# BoardB-Python.net
KiCad netlist of a schematic drawn in Altium Designer
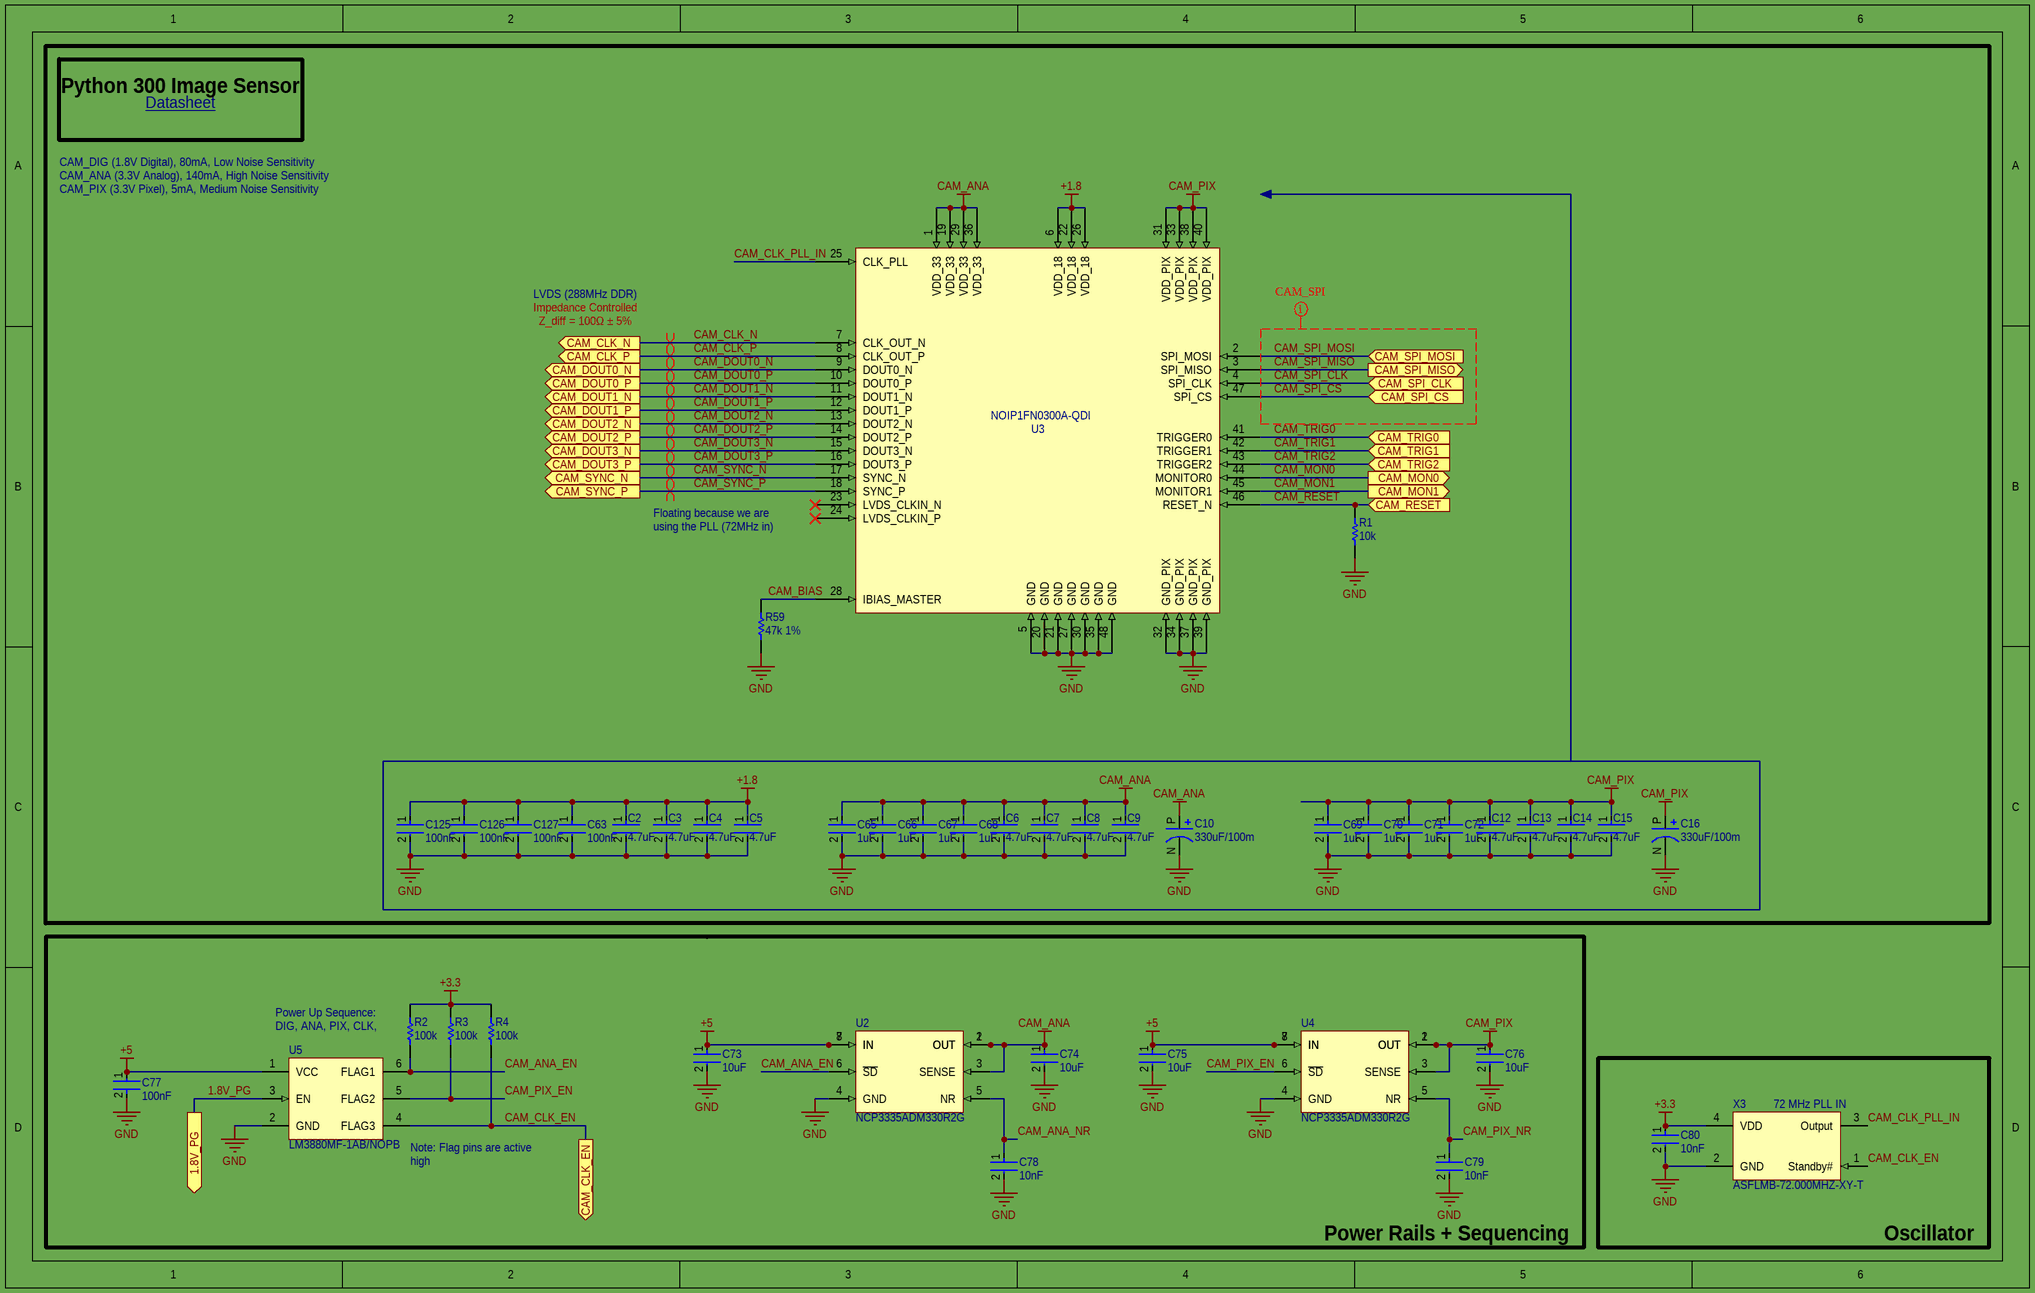
[diagram p0: BoardB-Python.SchDoc]

(export (version "E")
  (design (tool "Eeschema 10.0.6"))
  (components
    (comp (ref "C2")
      (value "4.7uF")
      (footprint "FP-GRM155-0_1-IPC_B")
      (description "Chip Multilayer Ceramic Capacitors for General Purpose, 0402, 4.7uF, X5R, 15%, 20%, 6.3V")
      (fields (field (name "VOLTAGE") "6.3V") (field (name "TOLERANCE") "20%"))
      (libsource (lib "Altium Content Vault") (part "11868f565c42a9108669ba33697ecf6"))
    )
    (comp (ref "C3")
      (value "4.7uF")
      (footprint "FP-GRM155-0_1-IPC_B")
      (description "Chip Multilayer Ceramic Capacitors for General Purpose, 0402, 4.7uF, X5R, 15%, 20%, 6.3V")
      (fields (field (name "VOLTAGE") "6.3V") (field (name "TOLERANCE") "20%"))
      (libsource (lib "Altium Content Vault") (part "11868f565c42a9108669ba33697ecf6"))
    )
    (comp (ref "C4")
      (value "4.7uF")
      (footprint "FP-GRM155-0_1-IPC_B")
      (description "Chip Multilayer Ceramic Capacitors for General Purpose, 0402, 4.7uF, X5R, 15%, 20%, 6.3V")
      (fields (field (name "VOLTAGE") "6.3V") (field (name "TOLERANCE") "20%"))
      (libsource (lib "Altium Content Vault") (part "11868f565c42a9108669ba33697ecf6"))
    )
    (comp (ref "C5")
      (value "4.7uF")
      (footprint "FP-GRM155-0_1-IPC_B")
      (description "Chip Multilayer Ceramic Capacitors for General Purpose, 0402, 4.7uF, X5R, 15%, 20%, 6.3V")
      (fields (field (name "VOLTAGE") "6.3V") (field (name "TOLERANCE") "20%"))
      (libsource (lib "Altium Content Vault") (part "11868f565c42a9108669ba33697ecf6"))
    )
    (comp (ref "C6")
      (value "4.7uF")
      (footprint "FP-GRM155-0_1-IPC_B")
      (description "Chip Multilayer Ceramic Capacitors for General Purpose, 0402, 4.7uF, X5R, 15%, 20%, 6.3V")
      (fields (field (name "VOLTAGE") "6.3V") (field (name "TOLERANCE") "20%"))
      (libsource (lib "Altium Content Vault") (part "11868f565c42a9108669ba33697ecf6"))
    )
    (comp (ref "C7")
      (value "4.7uF")
      (footprint "FP-GRM155-0_1-IPC_B")
      (description "Chip Multilayer Ceramic Capacitors for General Purpose, 0402, 4.7uF, X5R, 15%, 20%, 6.3V")
      (fields (field (name "VOLTAGE") "6.3V") (field (name "TOLERANCE") "20%"))
      (libsource (lib "Altium Content Vault") (part "11868f565c42a9108669ba33697ecf6"))
    )
    (comp (ref "C8")
      (value "4.7uF")
      (footprint "FP-GRM155-0_1-IPC_B")
      (description "Chip Multilayer Ceramic Capacitors for General Purpose, 0402, 4.7uF, X5R, 15%, 20%, 6.3V")
      (fields (field (name "VOLTAGE") "6.3V") (field (name "TOLERANCE") "20%"))
      (libsource (lib "Altium Content Vault") (part "11868f565c42a9108669ba33697ecf6"))
    )
    (comp (ref "C9")
      (value "4.7uF")
      (footprint "FP-GRM155-0_1-IPC_B")
      (description "Chip Multilayer Ceramic Capacitors for General Purpose, 0402, 4.7uF, X5R, 15%, 20%, 6.3V")
      (fields (field (name "VOLTAGE") "6.3V") (field (name "TOLERANCE") "20%"))
      (libsource (lib "Altium Content Vault") (part "11868f565c42a9108669ba33697ecf6"))
    )
    (comp (ref "C10")
      (value "330uF/100m")
      (footprint "NOSD337M004R0100")
      (description "330uF +/-20% 4 V dc SMD Niobium Capacitor; 7343-31 package; ESR 0.1Ohms NOS")
      (fields
        (field (name "MANUFACTURER") "Kyocera AVX")
        (field (name "MANUFACTURER PART NUMBER") "NOSD337M004R0100")
      )
      (libsource (lib "Virtex") (part "NOSD337M004R0100"))
    )
    (comp (ref "C12")
      (value "4.7uF")
      (footprint "FP-GRM155-0_1-IPC_B")
      (description "Chip Multilayer Ceramic Capacitors for General Purpose, 0402, 4.7uF, X5R, 15%, 20%, 6.3V")
      (fields (field (name "VOLTAGE") "6.3V") (field (name "TOLERANCE") "20%"))
      (libsource (lib "Altium Content Vault") (part "11868f565c42a9108669ba33697ecf6"))
    )
    (comp (ref "C13")
      (value "4.7uF")
      (footprint "FP-GRM155-0_1-IPC_B")
      (description "Chip Multilayer Ceramic Capacitors for General Purpose, 0402, 4.7uF, X5R, 15%, 20%, 6.3V")
      (fields (field (name "VOLTAGE") "6.3V") (field (name "TOLERANCE") "20%"))
      (libsource (lib "Altium Content Vault") (part "11868f565c42a9108669ba33697ecf6"))
    )
    (comp (ref "C14")
      (value "4.7uF")
      (footprint "FP-GRM155-0_1-IPC_B")
      (description "Chip Multilayer Ceramic Capacitors for General Purpose, 0402, 4.7uF, X5R, 15%, 20%, 6.3V")
      (fields (field (name "VOLTAGE") "6.3V") (field (name "TOLERANCE") "20%"))
      (libsource (lib "Altium Content Vault") (part "11868f565c42a9108669ba33697ecf6"))
    )
    (comp (ref "C15")
      (value "4.7uF")
      (footprint "FP-GRM155-0_1-IPC_B")
      (description "Chip Multilayer Ceramic Capacitors for General Purpose, 0402, 4.7uF, X5R, 15%, 20%, 6.3V")
      (fields (field (name "VOLTAGE") "6.3V") (field (name "TOLERANCE") "20%"))
      (libsource (lib "Altium Content Vault") (part "11868f565c42a9108669ba33697ecf6"))
    )
    (comp (ref "C16")
      (value "330uF/100m")
      (footprint "NOSD337M004R0100")
      (description "330uF +/-20% 4 V dc SMD Niobium Capacitor; 7343-31 package; ESR 0.1Ohms NOS")
      (fields
        (field (name "MANUFACTURER") "Kyocera AVX")
        (field (name "MANUFACTURER PART NUMBER") "NOSD337M004R0100")
      )
      (libsource (lib "Virtex") (part "NOSD337M004R0100"))
    )
    (comp (ref "C63")
      (value "100nF")
      (footprint "FP-C0402-BB-MFG")
      (description "CAP CER 0.1UF 10V X5R 0402")
      (fields (field (name "MANUFACTURER") "Kemet") (field (name "TOLERANCE") "0.1"))
      (libsource (lib "Altium Content Vault") (part "b4654b650e69147ec39a6b967a45e02"))
    )
    (comp (ref "C65")
      (value "1uF")
      (footprint "FP-GRM15-0_1-MFG")
      (description "CAP CER 1UF 10V X5R 0402")
      (fields
        (field (name "OCTOPART") "https://octopart.com/grm155r61a105ke15d-murata-197442")
        (field (name "MANUFACTURER PART NUMBER") "GRM155R61A105KE15D")
      )
      (libsource (lib "Altium Content Vault") (part "02cd4be3c70576c341d710602a673aa"))
    )
    (comp (ref "C66")
      (value "1uF")
      (footprint "FP-GRM15-0_1-MFG")
      (description "CAP CER 1UF 10V X5R 0402")
      (fields
        (field (name "OCTOPART") "https://octopart.com/grm155r61a105ke15d-murata-197442")
        (field (name "MANUFACTURER PART NUMBER") "GRM155R61A105KE15D")
      )
      (libsource (lib "Altium Content Vault") (part "02cd4be3c70576c341d710602a673aa"))
    )
    (comp (ref "C67")
      (value "1uF")
      (footprint "FP-GRM15-0_1-MFG")
      (description "CAP CER 1UF 10V X5R 0402")
      (fields
        (field (name "OCTOPART") "https://octopart.com/grm155r61a105ke15d-murata-197442")
        (field (name "MANUFACTURER PART NUMBER") "GRM155R61A105KE15D")
      )
      (libsource (lib "Altium Content Vault") (part "02cd4be3c70576c341d710602a673aa"))
    )
    (comp (ref "C68")
      (value "1uF")
      (footprint "FP-GRM15-0_1-MFG")
      (description "CAP CER 1UF 10V X5R 0402")
      (fields
        (field (name "OCTOPART") "https://octopart.com/grm155r61a105ke15d-murata-197442")
        (field (name "MANUFACTURER PART NUMBER") "GRM155R61A105KE15D")
      )
      (libsource (lib "Altium Content Vault") (part "02cd4be3c70576c341d710602a673aa"))
    )
    (comp (ref "C69")
      (value "1uF")
      (footprint "FP-GRM15-0_1-MFG")
      (description "CAP CER 1UF 10V X5R 0402")
      (fields
        (field (name "OCTOPART") "https://octopart.com/grm155r61a105ke15d-murata-197442")
        (field (name "MANUFACTURER PART NUMBER") "GRM155R61A105KE15D")
      )
      (libsource (lib "Altium Content Vault") (part "02cd4be3c70576c341d710602a673aa"))
    )
    (comp (ref "C70")
      (value "1uF")
      (footprint "FP-GRM15-0_1-MFG")
      (description "CAP CER 1UF 10V X5R 0402")
      (fields
        (field (name "OCTOPART") "https://octopart.com/grm155r61a105ke15d-murata-197442")
        (field (name "MANUFACTURER PART NUMBER") "GRM155R61A105KE15D")
      )
      (libsource (lib "Altium Content Vault") (part "02cd4be3c70576c341d710602a673aa"))
    )
    (comp (ref "C71")
      (value "1uF")
      (footprint "FP-GRM15-0_1-MFG")
      (description "CAP CER 1UF 10V X5R 0402")
      (fields
        (field (name "OCTOPART") "https://octopart.com/grm155r61a105ke15d-murata-197442")
        (field (name "MANUFACTURER PART NUMBER") "GRM155R61A105KE15D")
      )
      (libsource (lib "Altium Content Vault") (part "02cd4be3c70576c341d710602a673aa"))
    )
    (comp (ref "C72")
      (value "1uF")
      (footprint "FP-GRM15-0_1-MFG")
      (description "CAP CER 1UF 10V X5R 0402")
      (fields
        (field (name "OCTOPART") "https://octopart.com/grm155r61a105ke15d-murata-197442")
        (field (name "MANUFACTURER PART NUMBER") "GRM155R61A105KE15D")
      )
      (libsource (lib "Altium Content Vault") (part "02cd4be3c70576c341d710602a673aa"))
    )
    (comp (ref "C73")
      (value "10uF")
      (footprint "FP-CL05A106MP5NUNC-MFG")
      (description "CAP CER 10UF 10V X5R 0402")
      (fields
        (field (name "OCTOPART") "https://octopart.com/cl05a106mp5nunc-samsung-22457395")
        (field (name "TOLERANCE") "20%")
      )
      (libsource (lib "Altium Content Vault") (part "b4654b650e69147ec39a6b967a45e02"))
    )
    (comp (ref "C74")
      (value "10uF")
      (footprint "FP-CL05A106MP5NUNC-MFG")
      (description "CAP CER 10UF 10V X5R 0402")
      (fields
        (field (name "OCTOPART") "https://octopart.com/cl05a106mp5nunc-samsung-22457395")
        (field (name "TOLERANCE") "20%")
      )
      (libsource (lib "Altium Content Vault") (part "b4654b650e69147ec39a6b967a45e02"))
    )
    (comp (ref "C75")
      (value "10uF")
      (footprint "FP-CL05A106MP5NUNC-MFG")
      (description "CAP CER 10UF 10V X5R 0402")
      (fields
        (field (name "OCTOPART") "https://octopart.com/cl05a106mp5nunc-samsung-22457395")
        (field (name "TOLERANCE") "20%")
      )
      (libsource (lib "Altium Content Vault") (part "b4654b650e69147ec39a6b967a45e02"))
    )
    (comp (ref "C76")
      (value "10uF")
      (footprint "FP-CL05A106MP5NUNC-MFG")
      (description "CAP CER 10UF 10V X5R 0402")
      (fields
        (field (name "OCTOPART") "https://octopart.com/cl05a106mp5nunc-samsung-22457395")
        (field (name "TOLERANCE") "20%")
      )
      (libsource (lib "Altium Content Vault") (part "b4654b650e69147ec39a6b967a45e02"))
    )
    (comp (ref "C77")
      (value "100nF")
      (footprint "FP-GRM15-MFG")
      (description "CAP CER 0.1UF 16V X7R 0402")
      (fields (field (name "MANUFACTURER PART NUMBER") "GRM155R71C104KA88D") (field (name "TOLERANCE") "10%"))
      (libsource (lib "Altium Content Vault") (part "236180d848d6139a670b325ea6854c9"))
    )
    (comp (ref "C78")
      (value "10nF")
      (footprint "FP-CC0402-MFG")
      (description "CAP CER 10000PF 16V X7R 0402")
      (fields (field (name "MANUFACTURER PART NUMBER") "CC0402KRX7R7BB103") (field (name "TOLERANCE") "0.1"))
      (libsource (lib "Altium Content Vault") (part "11868f565c42a9108669ba33697ecf6"))
    )
    (comp (ref "C79")
      (value "10nF")
      (footprint "FP-CC0402-MFG")
      (description "CAP CER 10000PF 16V X7R 0402")
      (fields (field (name "MANUFACTURER PART NUMBER") "CC0402KRX7R7BB103") (field (name "TOLERANCE") "0.1"))
      (libsource (lib "Altium Content Vault") (part "11868f565c42a9108669ba33697ecf6"))
    )
    (comp (ref "C80")
      (value "10nF")
      (footprint "FP-CC0402-MFG")
      (description "CAP CER 10000PF 16V X7R 0402")
      (fields (field (name "MANUFACTURER PART NUMBER") "CC0402KRX7R7BB103") (field (name "TOLERANCE") "0.1"))
      (libsource (lib "Altium Content Vault") (part "11868f565c42a9108669ba33697ecf6"))
    )
    (comp (ref "C125")
      (value "100nF")
      (footprint "FP-C0402-BB-MFG")
      (description "CAP CER 0.1UF 10V X5R 0402")
      (fields (field (name "MANUFACTURER") "Kemet") (field (name "TOLERANCE") "0.1"))
      (libsource (lib "Altium Content Vault") (part "b4654b650e69147ec39a6b967a45e02"))
    )
    (comp (ref "C126")
      (value "100nF")
      (footprint "FP-C0402-BB-MFG")
      (description "CAP CER 0.1UF 10V X5R 0402")
      (fields (field (name "MANUFACTURER") "Kemet") (field (name "TOLERANCE") "0.1"))
      (libsource (lib "Altium Content Vault") (part "b4654b650e69147ec39a6b967a45e02"))
    )
    (comp (ref "C127")
      (value "100nF")
      (footprint "FP-C0402-BB-MFG")
      (description "CAP CER 0.1UF 10V X5R 0402")
      (fields (field (name "MANUFACTURER") "Kemet") (field (name "TOLERANCE") "0.1"))
      (libsource (lib "Altium Content Vault") (part "b4654b650e69147ec39a6b967a45e02"))
    )
    (comp (ref "R1")
      (value "10k")
      (footprint "RESC1005X40X25LL05T05")
      (description "Chip Resistor, 10 KOhm, +/- 1%, 0.1 W, -55 to 155 degC, 0402 (1005 Metric), RoHS, Tape and Reel")
      (fields (field (name "TOLERANCE") "1%") (field (name "MANUFACTURER") "Panasonic"))
      (libsource (lib "Altium Content Vault") (part "RES-2"))
    )
    (comp (ref "R2")
      (value "100k")
      (footprint "RESC1005X40X25ML05T10")
      (fields (field (name "PART NUMBER") "RC0402FR-07100KL") (field (name "MANUFACTURER") "Yageo / Phycomp"))
      (libsource (lib "Altium Content Vault") (part "RES"))
    )
    (comp (ref "R3")
      (value "100k")
      (footprint "RESC1005X40X25ML05T10")
      (fields (field (name "PART NUMBER") "RC0402FR-07100KL") (field (name "MANUFACTURER") "Yageo / Phycomp"))
      (libsource (lib "Altium Content Vault") (part "RES"))
    )
    (comp (ref "R4")
      (value "100k")
      (footprint "RESC1005X40X25ML05T10")
      (fields (field (name "PART NUMBER") "RC0402FR-07100KL") (field (name "MANUFACTURER") "Yageo / Phycomp"))
      (libsource (lib "Altium Content Vault") (part "RES"))
    )
    (comp (ref "R59")
      (value "47k 1%")
      (footprint "RESC1005X40X25NL05T05")
      (fields (field (name "PART NUMBER") "ERJ2RKF4702X") (field (name "MANUFACTURER") "Panasonic"))
      (libsource (lib "Altium Content Vault") (part "RES"))
    )
    (comp (ref "U2")
      (value "NCP3335ADM330R2G")
      (footprint "NCP3335ADM330R2G")
      (description "Linear Voltage Regulator, LDO, Ultra High Accuracy, Low Iq, 500 mA, V out : 3.3 V")
      (fields (field (name "MANUFACTURER") "ON Semiconductor"))
      (libsource (lib "Virtex") (part "NCP3335ADM330R2G"))
    )
    (comp (ref "U3")
      (value "NOIP1FN0300A-QDI")
      (footprint "NOIP1FN0300A-QDI")
      (description "IC IMAGE SENSOR 0.3MP 48LCC")
      (fields (field (name "MANUFACTURER") "ON Semiconductor"))
      (libsource (lib "Virtex") (part "NOIP1FN0300A-QDI"))
    )
    (comp (ref "U4")
      (value "NCP3335ADM330R2G")
      (footprint "NCP3335ADM330R2G")
      (description "Linear Voltage Regulator, LDO, Ultra High Accuracy, Low Iq, 500 mA, V out : 3.3 V")
      (fields (field (name "MANUFACTURER") "ON Semiconductor"))
      (libsource (lib "Virtex") (part "NCP3335ADM330R2G"))
    )
    (comp (ref "U5")
      (value "LM3880MF-1AB/NOPB")
      (footprint "DBV0006A_M")
      (description "Power Sequencer, 6-pin SOT-23, Pb-Free, 1000 Reel")
      (fields (field (name "MANUFACTURER") "Texas Instruments"))
      (libsource (lib "Altium Content Vault") (part "PM-CNTL-LM3880-6"))
    )
    (comp (ref "X3")
      (value "ASFLMB-72.000MHZ-XY-T")
      (footprint "ASFLMB-72.000MHZ-XY-T")
      (description "Silicon Oscillator 72MHz 15pF ±10ppm 4-Pin QFN T/R")
      (fields (field (name "MANUFACTURER") "Abracon"))
      (libsource (lib "Virtex") (part "ASFLMB-72.000MHZ-XY-T"))
    )
  )
  (nets
    (net (code "1") (name "+1.8") (class "Default")
      (node (ref "C125") (pin "1") (pinfunction "1_1") (pintype "passive"))
      (node (ref "C126") (pin "1") (pinfunction "1_1") (pintype "passive"))
      (node (ref "C127") (pin "1") (pinfunction "1_1") (pintype "passive"))
      (node (ref "C2") (pin "1") (pinfunction "1_1") (pintype "passive"))
      (node (ref "C3") (pin "1") (pinfunction "1_1") (pintype "passive"))
      (node (ref "C4") (pin "1") (pinfunction "1_1") (pintype "passive"))
      (node (ref "C5") (pin "1") (pinfunction "1_1") (pintype "passive"))
      (node (ref "C63") (pin "1") (pinfunction "1_1") (pintype "passive"))
      (node (ref "U3") (pin "22") (pinfunction "VDD_18_22") (pintype "input"))
      (node (ref "U3") (pin "26") (pinfunction "VDD_18_26") (pintype "input"))
      (node (ref "U3") (pin "6") (pinfunction "VDD_18_6") (pintype "input"))
    )
    (net (code "2") (name "+3.3") (class "Default")
      (node (ref "C80") (pin "1") (pinfunction "1_1") (pintype "passive"))
      (node (ref "R2") (pin "2") (pinfunction "2_2") (pintype "passive"))
      (node (ref "R3") (pin "2") (pinfunction "2_2") (pintype "passive"))
      (node (ref "R4") (pin "2") (pinfunction "2_2") (pintype "passive"))
      (node (ref "X3") (pin "4") (pinfunction "VDD_4") (pintype "power_in"))
    )
    (net (code "3") (name "+5") (class "Default")
      (node (ref "C73") (pin "1") (pinfunction "1_1") (pintype "passive"))
      (node (ref "C75") (pin "1") (pinfunction "1_1") (pintype "passive"))
      (node (ref "C77") (pin "1") (pinfunction "1_1") (pintype "passive"))
      (node (ref "U2") (pin "7") (pinfunction "IN_7") (pintype "input"))
      (node (ref "U2") (pin "8") (pinfunction "IN_8") (pintype "input"))
      (node (ref "U4") (pin "7") (pinfunction "IN_7") (pintype "input"))
      (node (ref "U4") (pin "8") (pinfunction "IN_8") (pintype "input"))
      (node (ref "U5") (pin "1") (pinfunction "VCC_1") (pintype "power_in"))
    )
    (net (code "4") (name "/1.8V_PG") (class "Default")
      (node (ref "U5") (pin "3") (pinfunction "EN_3") (pintype "input"))
    )
    (net (code "5") (name "/CAM_ANA_EN") (class "Default")
      (node (ref "R2") (pin "1") (pinfunction "1_1") (pintype "passive"))
      (node (ref "U2") (pin "6") (pinfunction "~{SD}_6") (pintype "input"))
      (node (ref "U5") (pin "6") (pinfunction "FLAG1_6") (pintype "open_collector"))
    )
    (net (code "6") (name "/CAM_ANA_NR") (class "Default")
      (node (ref "C78") (pin "1") (pinfunction "1_1") (pintype "passive"))
      (node (ref "U2") (pin "5") (pinfunction "NR_5") (pintype "input"))
    )
    (net (code "7") (name "/CAM_BIAS") (class "Default")
      (node (ref "R59") (pin "2") (pinfunction "2_2") (pintype "passive"))
      (node (ref "U3") (pin "28") (pinfunction "IBIAS_MASTER_28") (pintype "input"))
    )
    (net (code "8") (name "/CAM_CLK_EN") (class "Default")
      (node (ref "R4") (pin "1") (pinfunction "1_1") (pintype "passive"))
      (node (ref "U5") (pin "4") (pinfunction "FLAG3_4") (pintype "open_collector"))
      (node (ref "X3") (pin "1") (pinfunction "Standby#_1") (pintype "input"))
    )
    (net (code "9") (name "/CAM_CLK_N") (class "Default")
      (node (ref "U3") (pin "7") (pinfunction "CLK_OUT_N_7") (pintype "input"))
    )
    (net (code "10") (name "/CAM_CLK_P") (class "Default")
      (node (ref "U3") (pin "8") (pinfunction "CLK_OUT_P_8") (pintype "input"))
    )
    (net (code "11") (name "/CAM_CLK_PLL_IN") (class "Default")
      (node (ref "U3") (pin "25") (pinfunction "CLK_PLL_25") (pintype "input"))
      (node (ref "X3") (pin "3") (pinfunction "Output_3") (pintype "power_in"))
    )
    (net (code "12") (name "/CAM_DOUT0_N") (class "Default")
      (node (ref "U3") (pin "9") (pinfunction "DOUT0_N_9") (pintype "input"))
    )
    (net (code "13") (name "/CAM_DOUT0_P") (class "Default")
      (node (ref "U3") (pin "10") (pinfunction "DOUT0_P_10") (pintype "input"))
    )
    (net (code "14") (name "/CAM_DOUT1_N") (class "Default")
      (node (ref "U3") (pin "11") (pinfunction "DOUT1_N_11") (pintype "input"))
    )
    (net (code "15") (name "/CAM_DOUT1_P") (class "Default")
      (node (ref "U3") (pin "12") (pinfunction "DOUT1_P_12") (pintype "input"))
    )
    (net (code "16") (name "/CAM_DOUT2_N") (class "Default")
      (node (ref "U3") (pin "13") (pinfunction "DOUT2_N_13") (pintype "input"))
    )
    (net (code "17") (name "/CAM_DOUT2_P") (class "Default")
      (node (ref "U3") (pin "14") (pinfunction "DOUT2_P_14") (pintype "input"))
    )
    (net (code "18") (name "/CAM_DOUT3_N") (class "Default")
      (node (ref "U3") (pin "15") (pinfunction "DOUT3_N_15") (pintype "input"))
    )
    (net (code "19") (name "/CAM_DOUT3_P") (class "Default")
      (node (ref "U3") (pin "16") (pinfunction "DOUT3_P_16") (pintype "input"))
    )
    (net (code "20") (name "/CAM_MON0") (class "Default")
      (node (ref "U3") (pin "44") (pinfunction "MONITOR0_44") (pintype "input"))
    )
    (net (code "21") (name "/CAM_MON1") (class "Default")
      (node (ref "U3") (pin "45") (pinfunction "MONITOR1_45") (pintype "input"))
    )
    (net (code "22") (name "/CAM_PIX_EN") (class "Default")
      (node (ref "R3") (pin "1") (pinfunction "1_1") (pintype "passive"))
      (node (ref "U4") (pin "6") (pinfunction "~{SD}_6") (pintype "input"))
      (node (ref "U5") (pin "5") (pinfunction "FLAG2_5") (pintype "open_collector"))
    )
    (net (code "23") (name "/CAM_PIX_NR") (class "Default")
      (node (ref "C79") (pin "1") (pinfunction "1_1") (pintype "passive"))
      (node (ref "U4") (pin "5") (pinfunction "NR_5") (pintype "input"))
    )
    (net (code "24") (name "/CAM_RESET") (class "Default")
      (node (ref "R1") (pin "2") (pinfunction "2_2") (pintype "passive"))
      (node (ref "U3") (pin "46") (pinfunction "RESET_N_46") (pintype "input"))
    )
    (net (code "25") (name "/CAM_SPI_CLK") (class "Default")
      (node (ref "U3") (pin "4") (pinfunction "SPI_CLK_4") (pintype "input"))
    )
    (net (code "26") (name "/CAM_SPI_CS") (class "Default")
      (node (ref "U3") (pin "47") (pinfunction "SPI_CS_47") (pintype "input"))
    )
    (net (code "27") (name "/CAM_SPI_MISO") (class "Default")
      (node (ref "U3") (pin "3") (pinfunction "SPI_MISO_3") (pintype "input"))
    )
    (net (code "28") (name "/CAM_SPI_MOSI") (class "Default")
      (node (ref "U3") (pin "2") (pinfunction "SPI_MOSI_2") (pintype "input"))
    )
    (net (code "29") (name "/CAM_SYNC_N") (class "Default")
      (node (ref "U3") (pin "17") (pinfunction "SYNC_N_17") (pintype "input"))
    )
    (net (code "30") (name "/CAM_SYNC_P") (class "Default")
      (node (ref "U3") (pin "18") (pinfunction "SYNC_P_18") (pintype "input"))
    )
    (net (code "31") (name "/CAM_TRIG0") (class "Default")
      (node (ref "U3") (pin "41") (pinfunction "TRIGGER0_41") (pintype "input"))
    )
    (net (code "32") (name "/CAM_TRIG1") (class "Default")
      (node (ref "U3") (pin "42") (pinfunction "TRIGGER1_42") (pintype "input"))
    )
    (net (code "33") (name "/CAM_TRIG2") (class "Default")
      (node (ref "U3") (pin "43") (pinfunction "TRIGGER2_43") (pintype "input"))
    )
    (net (code "34") (name "CAM_ANA") (class "Default")
      (node (ref "C10") (pin "P") (pintype "passive"))
      (node (ref "C6") (pin "1") (pinfunction "1_1") (pintype "passive"))
      (node (ref "C65") (pin "1") (pinfunction "1_1") (pintype "passive"))
      (node (ref "C66") (pin "1") (pinfunction "1_1") (pintype "passive"))
      (node (ref "C67") (pin "1") (pinfunction "1_1") (pintype "passive"))
      (node (ref "C68") (pin "1") (pinfunction "1_1") (pintype "passive"))
      (node (ref "C7") (pin "1") (pinfunction "1_1") (pintype "passive"))
      (node (ref "C74") (pin "1") (pinfunction "1_1") (pintype "passive"))
      (node (ref "C8") (pin "1") (pinfunction "1_1") (pintype "passive"))
      (node (ref "C9") (pin "1") (pinfunction "1_1") (pintype "passive"))
      (node (ref "U2") (pin "1") (pinfunction "OUT_1") (pintype "input"))
      (node (ref "U2") (pin "2") (pinfunction "OUT_2") (pintype "input"))
      (node (ref "U2") (pin "3") (pinfunction "SENSE_3") (pintype "input"))
      (node (ref "U3") (pin "1") (pinfunction "VDD_33_1") (pintype "input"))
      (node (ref "U3") (pin "19") (pinfunction "VDD_33_19") (pintype "input"))
      (node (ref "U3") (pin "29") (pinfunction "VDD_33_29") (pintype "input"))
      (node (ref "U3") (pin "36") (pinfunction "VDD_33_36") (pintype "input"))
    )
    (net (code "35") (name "CAM_PIX") (class "Default")
      (node (ref "C12") (pin "1") (pinfunction "1_1") (pintype "passive"))
      (node (ref "C13") (pin "1") (pinfunction "1_1") (pintype "passive"))
      (node (ref "C14") (pin "1") (pinfunction "1_1") (pintype "passive"))
      (node (ref "C15") (pin "1") (pinfunction "1_1") (pintype "passive"))
      (node (ref "C16") (pin "P") (pintype "passive"))
      (node (ref "C69") (pin "1") (pinfunction "1_1") (pintype "passive"))
      (node (ref "C70") (pin "1") (pinfunction "1_1") (pintype "passive"))
      (node (ref "C71") (pin "1") (pinfunction "1_1") (pintype "passive"))
      (node (ref "C72") (pin "1") (pinfunction "1_1") (pintype "passive"))
      (node (ref "C76") (pin "1") (pinfunction "1_1") (pintype "passive"))
      (node (ref "U3") (pin "31") (pinfunction "VDD_PIX_31") (pintype "input"))
      (node (ref "U3") (pin "33") (pinfunction "VDD_PIX_33") (pintype "input"))
      (node (ref "U3") (pin "38") (pinfunction "VDD_PIX_38") (pintype "input"))
      (node (ref "U3") (pin "40") (pinfunction "VDD_PIX_40") (pintype "input"))
      (node (ref "U4") (pin "1") (pinfunction "OUT_1") (pintype "input"))
      (node (ref "U4") (pin "2") (pinfunction "OUT_2") (pintype "input"))
      (node (ref "U4") (pin "3") (pinfunction "SENSE_3") (pintype "input"))
    )
    (net (code "36") (name "GND") (class "Default")
      (node (ref "C10") (pin "N") (pintype "passive"))
      (node (ref "C12") (pin "2") (pinfunction "2_2") (pintype "passive"))
      (node (ref "C125") (pin "2") (pinfunction "2_2") (pintype "passive"))
      (node (ref "C126") (pin "2") (pinfunction "2_2") (pintype "passive"))
      (node (ref "C127") (pin "2") (pinfunction "2_2") (pintype "passive"))
      (node (ref "C13") (pin "2") (pinfunction "2_2") (pintype "passive"))
      (node (ref "C14") (pin "2") (pinfunction "2_2") (pintype "passive"))
      (node (ref "C15") (pin "2") (pinfunction "2_2") (pintype "passive"))
      (node (ref "C16") (pin "N") (pintype "passive"))
      (node (ref "C2") (pin "2") (pinfunction "2_2") (pintype "passive"))
      (node (ref "C3") (pin "2") (pinfunction "2_2") (pintype "passive"))
      (node (ref "C4") (pin "2") (pinfunction "2_2") (pintype "passive"))
      (node (ref "C5") (pin "2") (pinfunction "2_2") (pintype "passive"))
      (node (ref "C6") (pin "2") (pinfunction "2_2") (pintype "passive"))
      (node (ref "C63") (pin "2") (pinfunction "2_2") (pintype "passive"))
      (node (ref "C65") (pin "2") (pinfunction "2_2") (pintype "passive"))
      (node (ref "C66") (pin "2") (pinfunction "2_2") (pintype "passive"))
      (node (ref "C67") (pin "2") (pinfunction "2_2") (pintype "passive"))
      (node (ref "C68") (pin "2") (pinfunction "2_2") (pintype "passive"))
      (node (ref "C69") (pin "2") (pinfunction "2_2") (pintype "passive"))
      (node (ref "C7") (pin "2") (pinfunction "2_2") (pintype "passive"))
      (node (ref "C70") (pin "2") (pinfunction "2_2") (pintype "passive"))
      (node (ref "C71") (pin "2") (pinfunction "2_2") (pintype "passive"))
      (node (ref "C72") (pin "2") (pinfunction "2_2") (pintype "passive"))
      (node (ref "C73") (pin "2") (pinfunction "2_2") (pintype "passive"))
      (node (ref "C74") (pin "2") (pinfunction "2_2") (pintype "passive"))
      (node (ref "C75") (pin "2") (pinfunction "2_2") (pintype "passive"))
      (node (ref "C76") (pin "2") (pinfunction "2_2") (pintype "passive"))
      (node (ref "C77") (pin "2") (pinfunction "2_2") (pintype "passive"))
      (node (ref "C78") (pin "2") (pinfunction "2_2") (pintype "passive"))
      (node (ref "C79") (pin "2") (pinfunction "2_2") (pintype "passive"))
      (node (ref "C8") (pin "2") (pinfunction "2_2") (pintype "passive"))
      (node (ref "C80") (pin "2") (pinfunction "2_2") (pintype "passive"))
      (node (ref "C9") (pin "2") (pinfunction "2_2") (pintype "passive"))
      (node (ref "R1") (pin "1") (pinfunction "1_1") (pintype "passive"))
      (node (ref "R59") (pin "1") (pinfunction "1_1") (pintype "passive"))
      (node (ref "U2") (pin "4") (pinfunction "GND_4") (pintype "input"))
      (node (ref "U3") (pin "20") (pinfunction "GND_20") (pintype "input"))
      (node (ref "U3") (pin "21") (pinfunction "GND_21") (pintype "input"))
      (node (ref "U3") (pin "27") (pinfunction "GND_27") (pintype "input"))
      (node (ref "U3") (pin "30") (pinfunction "GND_30") (pintype "input"))
      (node (ref "U3") (pin "32") (pinfunction "GND_PIX_32") (pintype "input"))
      (node (ref "U3") (pin "34") (pinfunction "GND_PIX_34") (pintype "input"))
      (node (ref "U3") (pin "35") (pinfunction "GND_35") (pintype "input"))
      (node (ref "U3") (pin "37") (pinfunction "GND_PIX_37") (pintype "input"))
      (node (ref "U3") (pin "39") (pinfunction "GND_PIX_39") (pintype "input"))
      (node (ref "U3") (pin "48") (pinfunction "GND_48") (pintype "input"))
      (node (ref "U3") (pin "5") (pinfunction "GND_5") (pintype "input"))
      (node (ref "U4") (pin "4") (pinfunction "GND_4") (pintype "input"))
      (node (ref "U5") (pin "2") (pinfunction "GND_2") (pintype "power_in"))
      (node (ref "X3") (pin "2") (pinfunction "GND_2") (pintype "power_in"))
    )
    (net (code "37") (name "unconnected-(U3-LVDS_CLKIN_N-Pad23)") (class "Default")
      (node (ref "U3") (pin "23") (pinfunction "LVDS_CLKIN_N_23") (pintype "input+no_connect"))
    )
    (net (code "38") (name "unconnected-(U3-LVDS_CLKIN_P-Pad24)") (class "Default")
      (node (ref "U3") (pin "24") (pinfunction "LVDS_CLKIN_P_24") (pintype "input+no_connect"))
    )
  )
)
